# Power_MCU.net
KiCad netlist of a schematic drawn in Altium Designer
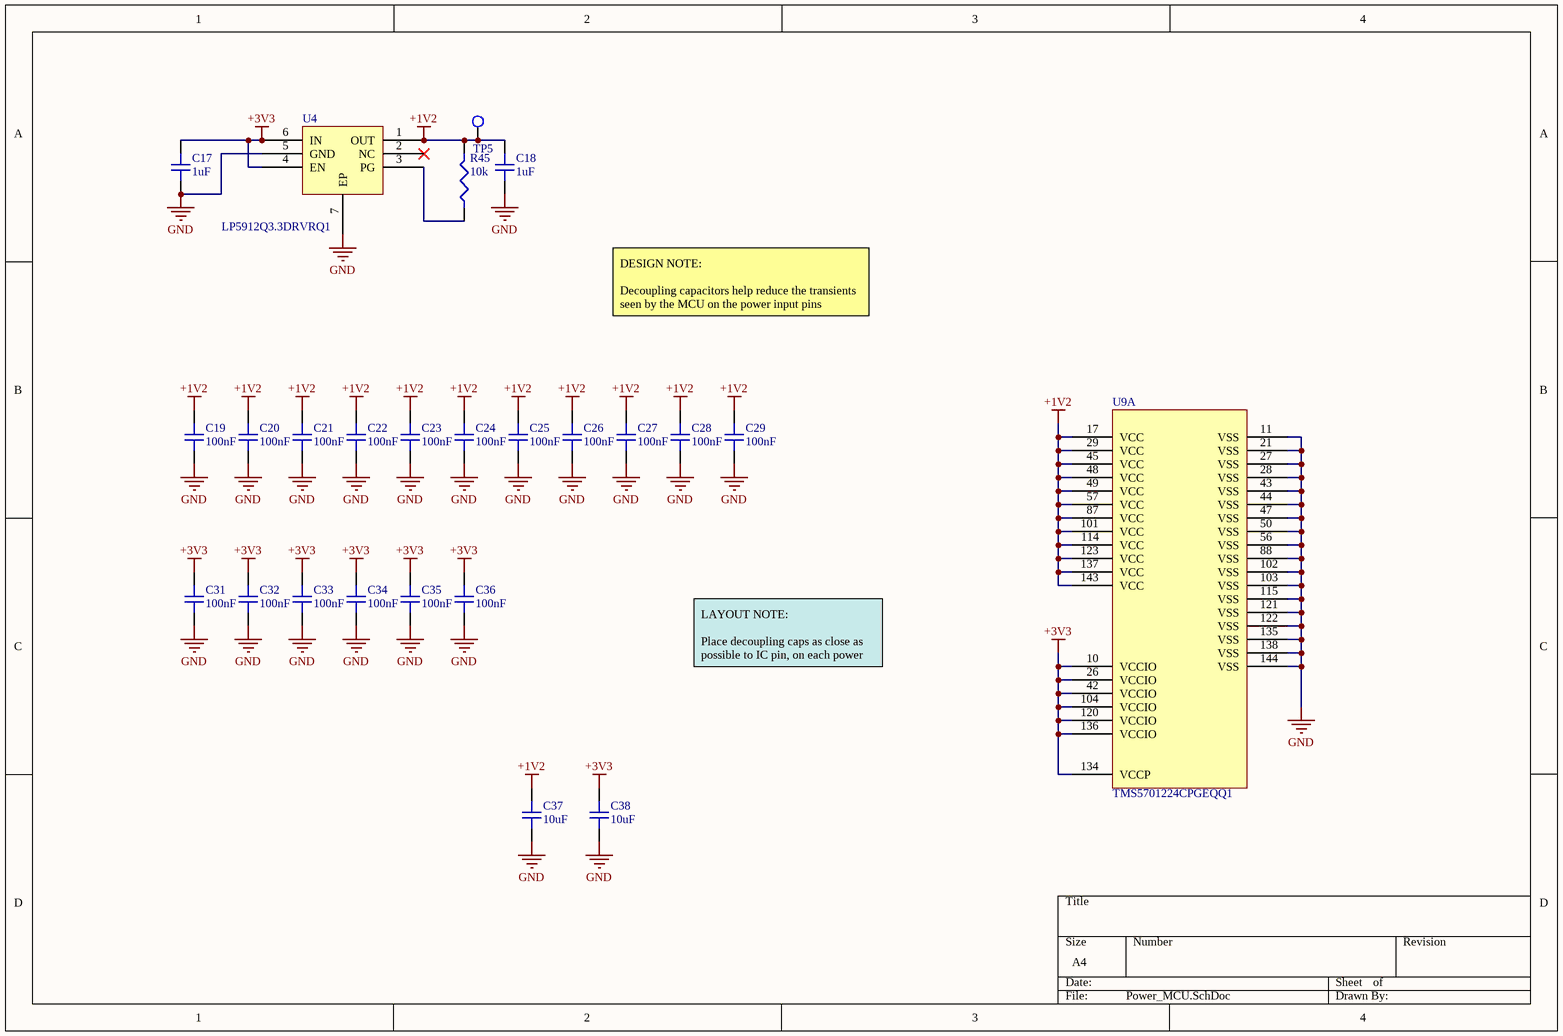
[diagram p0: Power_MCU.SchDoc]

(export (version "E")
  (design (tool "Eeschema 10.0.6"))
  (components
    (comp (ref "C17")
      (value "1uF")
      (footprint "C0805")
      (description "CAP CER 1UF 10V X7R 0805")
      (fields
        (field (name "MANUFACTURER") "Kyocera AVX")
        (field (name "MANUFACTURER PART NUMBER") "0805ZC105KAT2A")
      )
      (libsource (lib "PHANTOM_LIBRARY") (part "0805ZC105KAT2A"))
    )
    (comp (ref "C18")
      (value "1uF")
      (footprint "C0805")
      (description "CAP CER 1UF 10V X7R 0805")
      (fields
        (field (name "MANUFACTURER") "Kyocera AVX")
        (field (name "MANUFACTURER PART NUMBER") "0805ZC105KAT2A")
      )
      (libsource (lib "PHANTOM_LIBRARY") (part "0805ZC105KAT2A"))
    )
    (comp (ref "C19")
      (value "100nF")
      (footprint "PHANTOM_FOOTPRINTS:C0805")
      (description "MLCC SMD CAP 100nF 10Volts U2J 5%")
      (fields
        (field (name "MANUFACTURER") "Murata")
        (field (name "MANUFACTURER PART NUMBER") "GRM21B7U1A104JA01L")
      )
      (libsource (lib "PHANTOM_LIBRARY") (part "GRM21B7U1A104JA01L"))
    )
    (comp (ref "C20")
      (value "100nF")
      (footprint "PHANTOM_FOOTPRINTS:C0805")
      (description "MLCC SMD CAP 100nF 10Volts U2J 5%")
      (fields
        (field (name "MANUFACTURER") "Murata")
        (field (name "MANUFACTURER PART NUMBER") "GRM21B7U1A104JA01L")
      )
      (libsource (lib "PHANTOM_LIBRARY") (part "GRM21B7U1A104JA01L"))
    )
    (comp (ref "C21")
      (value "100nF")
      (footprint "PHANTOM_FOOTPRINTS:C0805")
      (description "MLCC SMD CAP 100nF 10Volts U2J 5%")
      (fields
        (field (name "MANUFACTURER") "Murata")
        (field (name "MANUFACTURER PART NUMBER") "GRM21B7U1A104JA01L")
      )
      (libsource (lib "PHANTOM_LIBRARY") (part "GRM21B7U1A104JA01L"))
    )
    (comp (ref "C22")
      (value "100nF")
      (footprint "PHANTOM_FOOTPRINTS:C0805")
      (description "MLCC SMD CAP 100nF 10Volts U2J 5%")
      (fields
        (field (name "MANUFACTURER") "Murata")
        (field (name "MANUFACTURER PART NUMBER") "GRM21B7U1A104JA01L")
      )
      (libsource (lib "PHANTOM_LIBRARY") (part "GRM21B7U1A104JA01L"))
    )
    (comp (ref "C23")
      (value "100nF")
      (footprint "PHANTOM_FOOTPRINTS:C0805")
      (description "MLCC SMD CAP 100nF 10Volts U2J 5%")
      (fields
        (field (name "MANUFACTURER") "Murata")
        (field (name "MANUFACTURER PART NUMBER") "GRM21B7U1A104JA01L")
      )
      (libsource (lib "PHANTOM_LIBRARY") (part "GRM21B7U1A104JA01L"))
    )
    (comp (ref "C24")
      (value "100nF")
      (footprint "PHANTOM_FOOTPRINTS:C0805")
      (description "MLCC SMD CAP 100nF 10Volts U2J 5%")
      (fields
        (field (name "MANUFACTURER") "Murata")
        (field (name "MANUFACTURER PART NUMBER") "GRM21B7U1A104JA01L")
      )
      (libsource (lib "PHANTOM_LIBRARY") (part "GRM21B7U1A104JA01L"))
    )
    (comp (ref "C25")
      (value "100nF")
      (footprint "PHANTOM_FOOTPRINTS:C0805")
      (description "MLCC SMD CAP 100nF 10Volts U2J 5%")
      (fields
        (field (name "MANUFACTURER") "Murata")
        (field (name "MANUFACTURER PART NUMBER") "GRM21B7U1A104JA01L")
      )
      (libsource (lib "PHANTOM_LIBRARY") (part "GRM21B7U1A104JA01L"))
    )
    (comp (ref "C26")
      (value "100nF")
      (footprint "PHANTOM_FOOTPRINTS:C0805")
      (description "MLCC SMD CAP 100nF 10Volts U2J 5%")
      (fields
        (field (name "MANUFACTURER") "Murata")
        (field (name "MANUFACTURER PART NUMBER") "GRM21B7U1A104JA01L")
      )
      (libsource (lib "PHANTOM_LIBRARY") (part "GRM21B7U1A104JA01L"))
    )
    (comp (ref "C27")
      (value "100nF")
      (footprint "PHANTOM_FOOTPRINTS:C0805")
      (description "MLCC SMD CAP 100nF 10Volts U2J 5%")
      (fields
        (field (name "MANUFACTURER") "Murata")
        (field (name "MANUFACTURER PART NUMBER") "GRM21B7U1A104JA01L")
      )
      (libsource (lib "PHANTOM_LIBRARY") (part "GRM21B7U1A104JA01L"))
    )
    (comp (ref "C28")
      (value "100nF")
      (footprint "PHANTOM_FOOTPRINTS:C0805")
      (description "MLCC SMD CAP 100nF 10Volts U2J 5%")
      (fields
        (field (name "MANUFACTURER") "Murata")
        (field (name "MANUFACTURER PART NUMBER") "GRM21B7U1A104JA01L")
      )
      (libsource (lib "PHANTOM_LIBRARY") (part "GRM21B7U1A104JA01L"))
    )
    (comp (ref "C29")
      (value "100nF")
      (footprint "PHANTOM_FOOTPRINTS:C0805")
      (description "MLCC SMD CAP 100nF 10Volts U2J 5%")
      (fields
        (field (name "MANUFACTURER") "Murata")
        (field (name "MANUFACTURER PART NUMBER") "GRM21B7U1A104JA01L")
      )
      (libsource (lib "PHANTOM_LIBRARY") (part "GRM21B7U1A104JA01L"))
    )
    (comp (ref "C31")
      (value "100nF")
      (footprint "PHANTOM_FOOTPRINTS:C0805")
      (description "MLCC SMD CAP 100nF 10Volts U2J 5%")
      (fields
        (field (name "MANUFACTURER") "Murata")
        (field (name "MANUFACTURER PART NUMBER") "GRM21B7U1A104JA01L")
      )
      (libsource (lib "PHANTOM_LIBRARY") (part "GRM21B7U1A104JA01L"))
    )
    (comp (ref "C32")
      (value "100nF")
      (footprint "PHANTOM_FOOTPRINTS:C0805")
      (description "MLCC SMD CAP 100nF 10Volts U2J 5%")
      (fields
        (field (name "MANUFACTURER") "Murata")
        (field (name "MANUFACTURER PART NUMBER") "GRM21B7U1A104JA01L")
      )
      (libsource (lib "PHANTOM_LIBRARY") (part "GRM21B7U1A104JA01L"))
    )
    (comp (ref "C33")
      (value "100nF")
      (footprint "PHANTOM_FOOTPRINTS:C0805")
      (description "MLCC SMD CAP 100nF 10Volts U2J 5%")
      (fields
        (field (name "MANUFACTURER") "Murata")
        (field (name "MANUFACTURER PART NUMBER") "GRM21B7U1A104JA01L")
      )
      (libsource (lib "PHANTOM_LIBRARY") (part "GRM21B7U1A104JA01L"))
    )
    (comp (ref "C34")
      (value "100nF")
      (footprint "PHANTOM_FOOTPRINTS:C0805")
      (description "MLCC SMD CAP 100nF 10Volts U2J 5%")
      (fields
        (field (name "MANUFACTURER") "Murata")
        (field (name "MANUFACTURER PART NUMBER") "GRM21B7U1A104JA01L")
      )
      (libsource (lib "PHANTOM_LIBRARY") (part "GRM21B7U1A104JA01L"))
    )
    (comp (ref "C35")
      (value "100nF")
      (footprint "PHANTOM_FOOTPRINTS:C0805")
      (description "MLCC SMD CAP 100nF 10Volts U2J 5%")
      (fields
        (field (name "MANUFACTURER") "Murata")
        (field (name "MANUFACTURER PART NUMBER") "GRM21B7U1A104JA01L")
      )
      (libsource (lib "PHANTOM_LIBRARY") (part "GRM21B7U1A104JA01L"))
    )
    (comp (ref "C36")
      (value "100nF")
      (footprint "PHANTOM_FOOTPRINTS:C0805")
      (description "MLCC SMD CAP 100nF 10Volts U2J 5%")
      (fields
        (field (name "MANUFACTURER") "Murata")
        (field (name "MANUFACTURER PART NUMBER") "GRM21B7U1A104JA01L")
      )
      (libsource (lib "PHANTOM_LIBRARY") (part "GRM21B7U1A104JA01L"))
    )
    (comp (ref "C37")
      (value "10uF")
      (footprint "TANT_10u")
      (fields
        (field (name "MANUFACTURER") "Kyocera AVX")
        (field (name "MANUFACTURER PART NUMBER") "F381A106MMA")
        (field (name "TOLERANCE") "20%")
      )
      (libsource (lib "PHANTOM_LIBRARY") (part "F381A106MMA"))
    )
    (comp (ref "C38")
      (value "10uF")
      (footprint "TANT_10u")
      (fields
        (field (name "MANUFACTURER") "Kyocera AVX")
        (field (name "MANUFACTURER PART NUMBER") "F381A106MMA")
        (field (name "TOLERANCE") "20%")
      )
      (libsource (lib "PHANTOM_LIBRARY") (part "F381A106MMA"))
    )
    (comp (ref "R45")
      (value "10k")
      (footprint "R0805")
      (description "RES SMD 10K OHM 1% 1/8W 0805")
      (fields
        (field (name "MANUFACTURER") "Yageo Phycomp")
        (field (name "MANUFACTURER PART NUMBER") "RC0805FR-071KL")
      )
      (libsource (lib "PHANTOM_LIBRARY") (part "RC0805FR-071KL"))
    )
    (comp (ref "TP5")
      (value "5015")
      (footprint "TP_HOOK")
      (description "TEST POINT, PCB, SMT")
      (fields (field (name "MANUFACTURER") "Keystone Electronics"))
      (libsource (lib "PHANTOM_LIBRARY") (part "5015"))
    )
    (comp (ref "U4")
      (value "LP5912Q3.3DRVRQ1")
      (footprint "WSON")
      (description "IC REG LDO 3.3V 0.5A")
      (fields (field (name "MANUFACTURER") "Texas Instruments"))
      (libsource (lib "PHANTOM_LIBRARY") (part "LP5912Q3.3DRVRQ1"))
    )
    (comp (ref "U9")
      (value "TMS5701224CPGEQQ1")
      (footprint "LQFP-144")
      (description "ARM CORTEX R4 LOCK STEP HERCULES MCU")
      (fields (field (name "MANUFACTURER") "Texas Instruments"))
      (libsource (lib "PHANTOM_LIBRARY") (part "TMS5701224CPGEQQ1"))
    )
  )
  (nets
    (net (code "1") (name "+1V2") (class "Default")
      (node (ref "C18") (pin "2") (pinfunction "2_2") (pintype "passive"))
      (node (ref "C19") (pin "2") (pinfunction "2_2") (pintype "passive"))
      (node (ref "C20") (pin "2") (pinfunction "2_2") (pintype "passive"))
      (node (ref "C21") (pin "2") (pinfunction "2_2") (pintype "passive"))
      (node (ref "C22") (pin "2") (pinfunction "2_2") (pintype "passive"))
      (node (ref "C23") (pin "2") (pinfunction "2_2") (pintype "passive"))
      (node (ref "C24") (pin "2") (pinfunction "2_2") (pintype "passive"))
      (node (ref "C25") (pin "2") (pinfunction "2_2") (pintype "passive"))
      (node (ref "C26") (pin "2") (pinfunction "2_2") (pintype "passive"))
      (node (ref "C27") (pin "2") (pinfunction "2_2") (pintype "passive"))
      (node (ref "C28") (pin "2") (pinfunction "2_2") (pintype "passive"))
      (node (ref "C29") (pin "2") (pinfunction "2_2") (pintype "passive"))
      (node (ref "C37") (pin "2") (pinfunction "2_2") (pintype "passive"))
      (node (ref "R45") (pin "2") (pinfunction "2_2") (pintype "passive"))
      (node (ref "TP5") (pin "1") (pinfunction "1_1") (pintype "passive"))
      (node (ref "U4") (pin "1") (pinfunction "OUT_1") (pintype "passive"))
      (node (ref "U9") (pin "101") (pinfunction "VCC_101") (pintype "passive"))
      (node (ref "U9") (pin "114") (pinfunction "VCC_114") (pintype "passive"))
      (node (ref "U9") (pin "123") (pinfunction "VCC_123") (pintype "passive"))
      (node (ref "U9") (pin "137") (pinfunction "VCC_137") (pintype "passive"))
      (node (ref "U9") (pin "143") (pinfunction "VCC_143") (pintype "passive"))
      (node (ref "U9") (pin "17") (pinfunction "VCC_17") (pintype "passive"))
      (node (ref "U9") (pin "29") (pinfunction "VCC_29") (pintype "passive"))
      (node (ref "U9") (pin "45") (pinfunction "VCC_45") (pintype "passive"))
      (node (ref "U9") (pin "48") (pinfunction "VCC_48") (pintype "passive"))
      (node (ref "U9") (pin "49") (pinfunction "VCC_49") (pintype "passive"))
      (node (ref "U9") (pin "57") (pinfunction "VCC_57") (pintype "passive"))
      (node (ref "U9") (pin "87") (pinfunction "VCC_87") (pintype "passive"))
    )
    (net (code "2") (name "+3V3") (class "Default")
      (node (ref "C17") (pin "2") (pinfunction "2_2") (pintype "passive"))
      (node (ref "C31") (pin "2") (pinfunction "2_2") (pintype "passive"))
      (node (ref "C32") (pin "2") (pinfunction "2_2") (pintype "passive"))
      (node (ref "C33") (pin "2") (pinfunction "2_2") (pintype "passive"))
      (node (ref "C34") (pin "2") (pinfunction "2_2") (pintype "passive"))
      (node (ref "C35") (pin "2") (pinfunction "2_2") (pintype "passive"))
      (node (ref "C36") (pin "2") (pinfunction "2_2") (pintype "passive"))
      (node (ref "C38") (pin "2") (pinfunction "2_2") (pintype "passive"))
      (node (ref "U4") (pin "4") (pinfunction "EN_4") (pintype "passive"))
      (node (ref "U4") (pin "6") (pinfunction "IN_6") (pintype "passive"))
      (node (ref "U9") (pin "10") (pinfunction "VCCIO_10") (pintype "passive"))
      (node (ref "U9") (pin "104") (pinfunction "VCCIO_104") (pintype "passive"))
      (node (ref "U9") (pin "120") (pinfunction "VCCIO_120") (pintype "passive"))
      (node (ref "U9") (pin "134") (pinfunction "VCCP_134") (pintype "passive"))
      (node (ref "U9") (pin "136") (pinfunction "VCCIO_136") (pintype "passive"))
      (node (ref "U9") (pin "26") (pinfunction "VCCIO_26") (pintype "passive"))
      (node (ref "U9") (pin "42") (pinfunction "VCCIO_42") (pintype "passive"))
    )
    (net (code "3") (name "GND") (class "Default")
      (node (ref "C17") (pin "1") (pinfunction "1_1") (pintype "passive"))
      (node (ref "C18") (pin "1") (pinfunction "1_1") (pintype "passive"))
      (node (ref "C19") (pin "1") (pinfunction "1_1") (pintype "passive"))
      (node (ref "C20") (pin "1") (pinfunction "1_1") (pintype "passive"))
      (node (ref "C21") (pin "1") (pinfunction "1_1") (pintype "passive"))
      (node (ref "C22") (pin "1") (pinfunction "1_1") (pintype "passive"))
      (node (ref "C23") (pin "1") (pinfunction "1_1") (pintype "passive"))
      (node (ref "C24") (pin "1") (pinfunction "1_1") (pintype "passive"))
      (node (ref "C25") (pin "1") (pinfunction "1_1") (pintype "passive"))
      (node (ref "C26") (pin "1") (pinfunction "1_1") (pintype "passive"))
      (node (ref "C27") (pin "1") (pinfunction "1_1") (pintype "passive"))
      (node (ref "C28") (pin "1") (pinfunction "1_1") (pintype "passive"))
      (node (ref "C29") (pin "1") (pinfunction "1_1") (pintype "passive"))
      (node (ref "C31") (pin "1") (pinfunction "1_1") (pintype "passive"))
      (node (ref "C32") (pin "1") (pinfunction "1_1") (pintype "passive"))
      (node (ref "C33") (pin "1") (pinfunction "1_1") (pintype "passive"))
      (node (ref "C34") (pin "1") (pinfunction "1_1") (pintype "passive"))
      (node (ref "C35") (pin "1") (pinfunction "1_1") (pintype "passive"))
      (node (ref "C36") (pin "1") (pinfunction "1_1") (pintype "passive"))
      (node (ref "C37") (pin "1") (pinfunction "1_1") (pintype "passive"))
      (node (ref "C38") (pin "1") (pinfunction "1_1") (pintype "passive"))
      (node (ref "U4") (pin "5") (pinfunction "GND_5") (pintype "passive"))
      (node (ref "U4") (pin "7") (pinfunction "EP_7") (pintype "passive"))
      (node (ref "U9") (pin "102") (pinfunction "VSS_102") (pintype "passive"))
      (node (ref "U9") (pin "103") (pinfunction "VSS_103") (pintype "passive"))
      (node (ref "U9") (pin "11") (pinfunction "VSS_11") (pintype "passive"))
      (node (ref "U9") (pin "115") (pinfunction "VSS_115") (pintype "passive"))
      (node (ref "U9") (pin "121") (pinfunction "VSS_121") (pintype "passive"))
      (node (ref "U9") (pin "122") (pinfunction "VSS_122") (pintype "passive"))
      (node (ref "U9") (pin "135") (pinfunction "VSS_135") (pintype "passive"))
      (node (ref "U9") (pin "138") (pinfunction "VSS_138") (pintype "passive"))
      (node (ref "U9") (pin "144") (pinfunction "VSS_144") (pintype "passive"))
      (node (ref "U9") (pin "21") (pinfunction "VSS_21") (pintype "passive"))
      (node (ref "U9") (pin "27") (pinfunction "VSS_27") (pintype "passive"))
      (node (ref "U9") (pin "28") (pinfunction "VSS_28") (pintype "passive"))
      (node (ref "U9") (pin "43") (pinfunction "VSS_43") (pintype "passive"))
      (node (ref "U9") (pin "44") (pinfunction "VSS_44") (pintype "passive"))
      (node (ref "U9") (pin "47") (pinfunction "VSS_47") (pintype "passive"))
      (node (ref "U9") (pin "50") (pinfunction "VSS_50") (pintype "passive"))
      (node (ref "U9") (pin "56") (pinfunction "VSS_56") (pintype "passive"))
      (node (ref "U9") (pin "88") (pinfunction "VSS_88") (pintype "passive"))
    )
    (net (code "4") (name "Net-(U4-PG)") (class "Default")
      (node (ref "R45") (pin "1") (pinfunction "1_1") (pintype "passive"))
      (node (ref "U4") (pin "3") (pinfunction "PG_3") (pintype "passive"))
    )
    (net (code "5") (name "unconnected-(U4-NC-Pad2)") (class "Default")
      (node (ref "U4") (pin "2") (pinfunction "NC_2") (pintype "passive+no_connect"))
    )
  )
)
